# STM32F4DD.net
KiCad netlist of a schematic drawn in Altium Designer
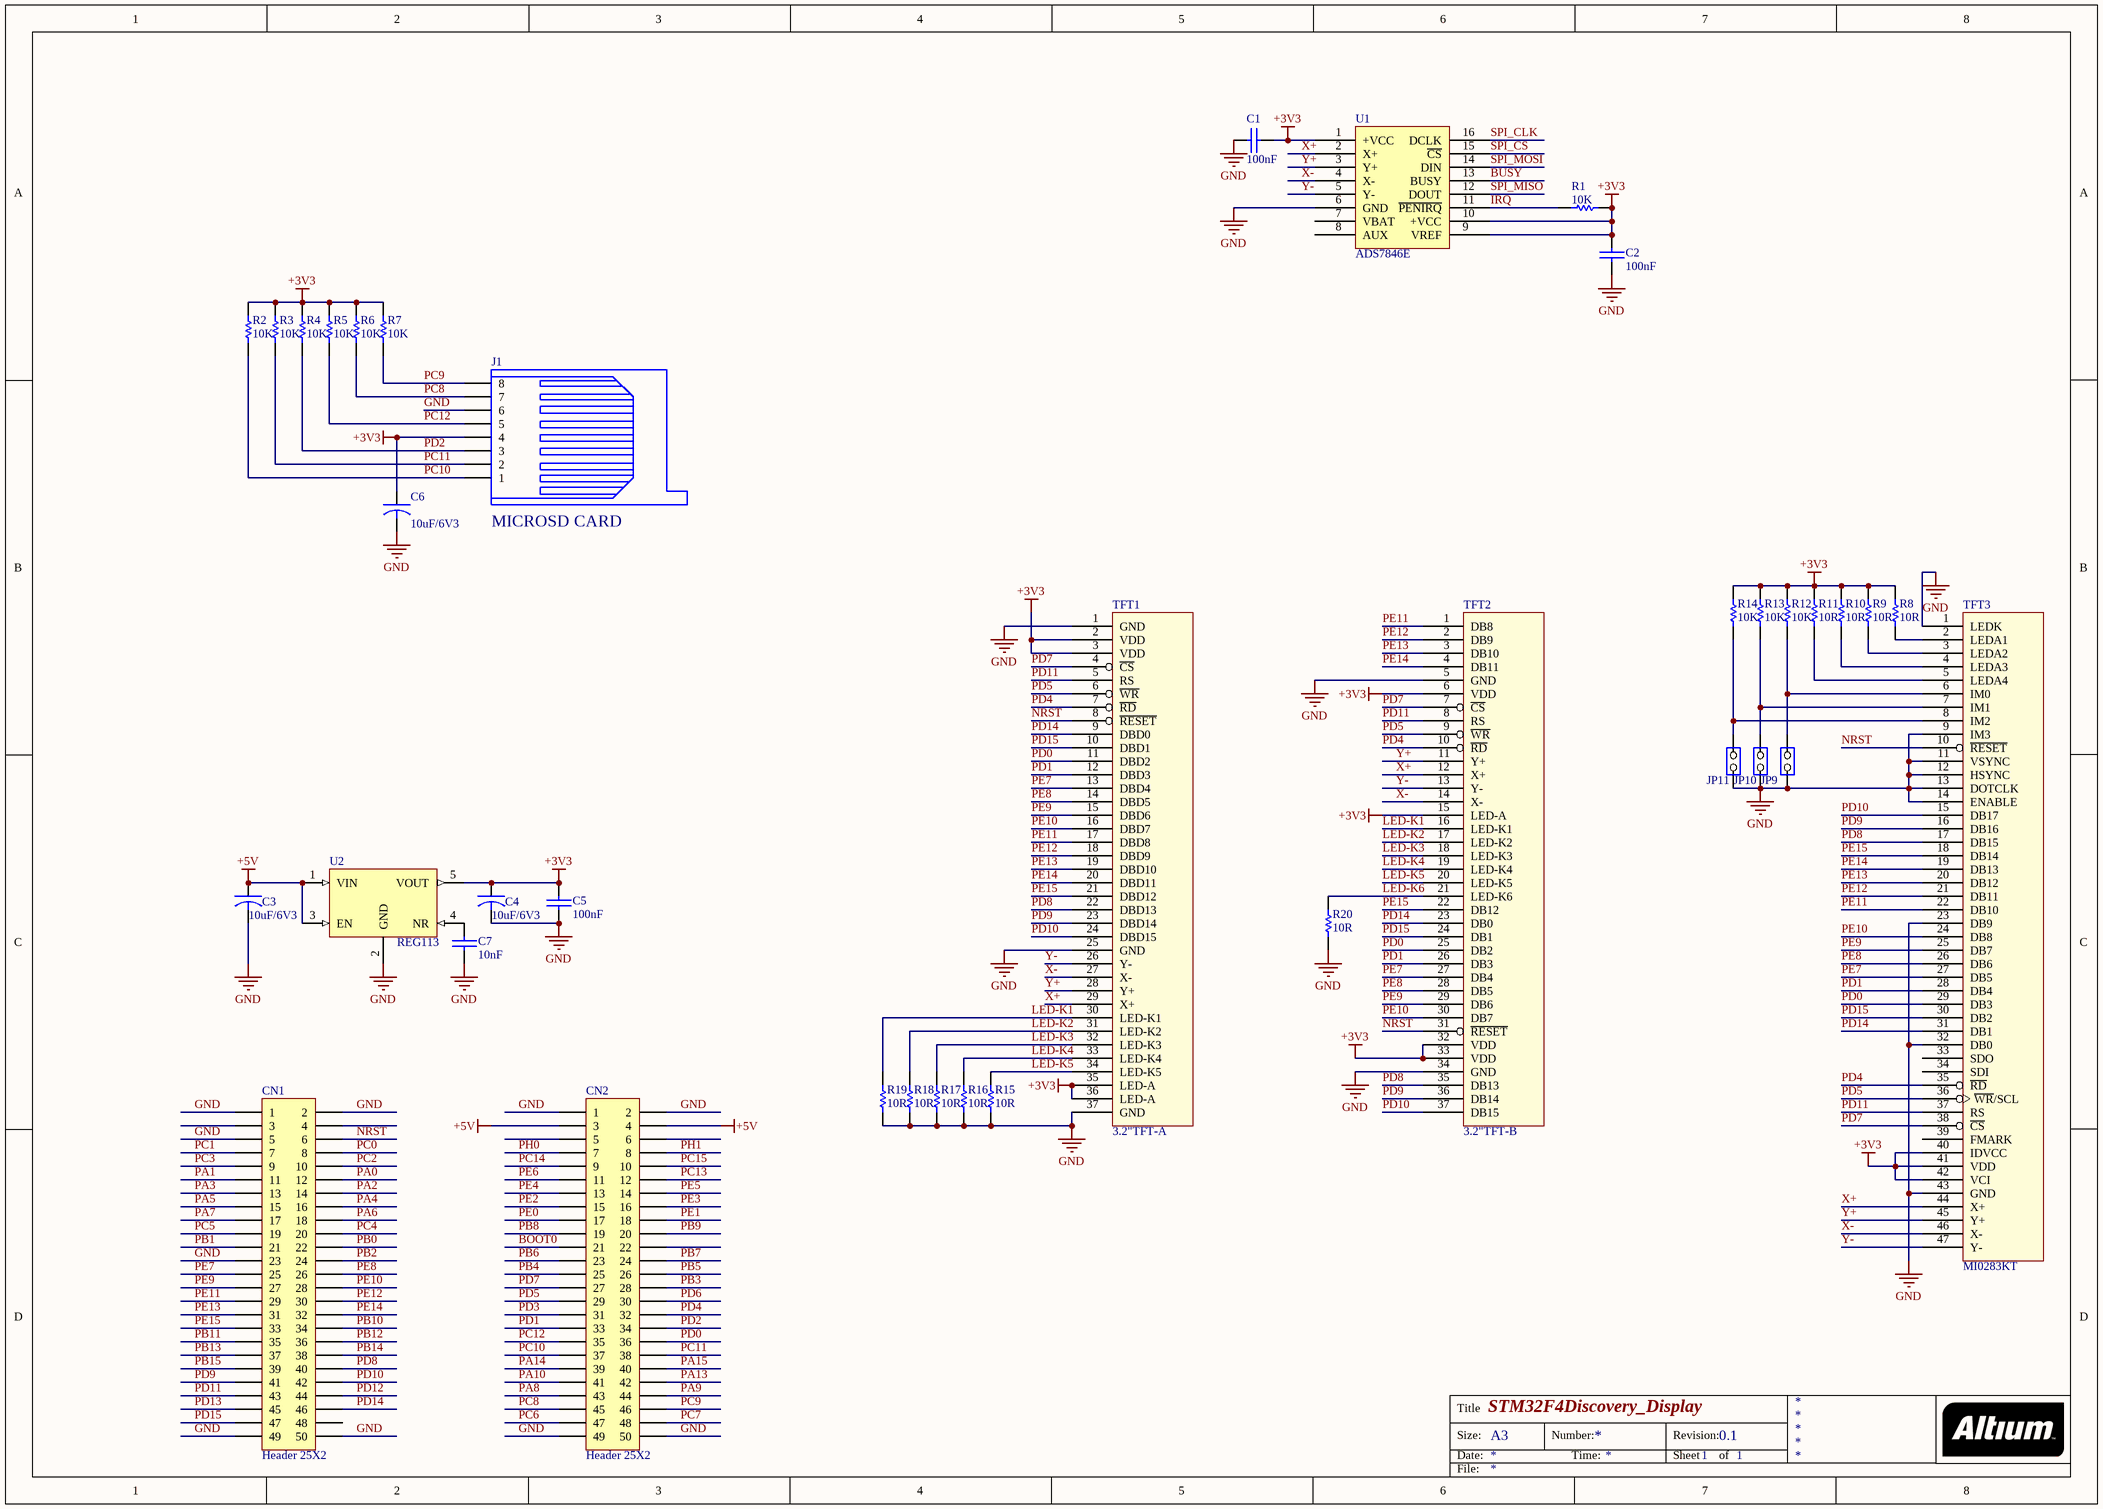
[diagram p0: STM32F4DD.SchDoc]

(export (version "E")
  (design (tool "Eeschema 10.0.6"))
  (components
    (comp (ref "C1")
      (value "100nF")
      (footprint "CAPC1608N")
      (description "Capacitor")
      (libsource (lib "*") (part "CAP"))
    )
    (comp (ref "C2")
      (value "100nF")
      (footprint "CAPC1608N")
      (description "Capacitor")
      (libsource (lib "*") (part "CAP"))
    )
    (comp (ref "C3")
      (value "10uF/6V3")
      (footprint "TC3528-1411")
      (description "Capacitor")
      (fields (field (name "MANUFACTURER") "VISHAY SPRAGUE"))
      (libsource (lib "DAU_Addition") (part "CAPACITOR"))
    )
    (comp (ref "C4")
      (value "10uF/6V3")
      (footprint "TC3528-1411")
      (description "Capacitor")
      (fields (field (name "MANUFACTURER") "VISHAY SPRAGUE"))
      (libsource (lib "DAU_Addition") (part "CAPACITOR"))
    )
    (comp (ref "C5")
      (value "100nF")
      (footprint "CAPC1608N")
      (description "Capacitor")
      (libsource (lib "*") (part "CAP"))
    )
    (comp (ref "C6")
      (value "10uF/6V3")
      (footprint "TC3528-1411")
      (description "Capacitor")
      (fields (field (name "MANUFACTURER") "VISHAY SPRAGUE"))
      (libsource (lib "DAU_Addition") (part "CAPACITOR"))
    )
    (comp (ref "C7")
      (value "10nF")
      (footprint "CAPC1608N")
      (description "Capacitor 10nF")
      (libsource (lib "*") (part "CAP"))
    )
    (comp (ref "CN1")
      (value "Header 25X2")
      (footprint "HDR2X25-TH-SMD")
      (description "Header, 25-Pin, Dual row")
      (fields (field (name "PUBLISHER") "Altium Limited"))
      (libsource (lib "Miscellaneous Connectors") (part "Header 25X2"))
    )
    (comp (ref "CN2")
      (value "Header 25X2")
      (footprint "HDR2X25-TH-SMD")
      (description "Header, 25-Pin, Dual row")
      (fields (field (name "PUBLISHER") "Altium Limited"))
      (libsource (lib "Miscellaneous Connectors") (part "Header 25X2"))
    )
    (comp (ref "J1")
      (value "TFMS08TK-PP")
      (footprint "MEM2060")
      (description "MICRO SD CARD CONNECTOR, PUSH/PUSH TYPE")
      (libsource (lib "*") (part "SMS016AFA5E"))
    )
    (comp (ref "JP9")
      (value "~")
      (footprint "Solder Jumper - NO")
      (description "BOARD-BOARD CONNECTOR HEADER, 2WAY, 1ROW")
      (fields (field (name "MANUFACTURER") "GCT"))
      (libsource (lib "*") (part "JP2"))
    )
    (comp (ref "JP10")
      (value "~")
      (footprint "Solder Jumper - NO")
      (description "BOARD-BOARD CONNECTOR HEADER, 2WAY, 1ROW")
      (fields (field (name "MANUFACTURER") "GCT"))
      (libsource (lib "*") (part "JP2"))
    )
    (comp (ref "JP11")
      (value "~")
      (footprint "Solder Jumper - NO")
      (description "BOARD-BOARD CONNECTOR HEADER, 2WAY, 1ROW")
      (fields (field (name "MANUFACTURER") "GCT"))
      (libsource (lib "*") (part "JP2"))
    )
    (comp (ref "R1")
      (value "10K")
      (footprint "RESC1608N")
      (description "Resistor")
      (fields (field (name "PUBLISHER") "Altium Limited"))
      (libsource (lib "Miscellaneous Devices") (part "Res1"))
    )
    (comp (ref "R2")
      (value "10K")
      (footprint "RESC1608N")
      (description "Resistor")
      (fields (field (name "PUBLISHER") "Altium Limited"))
      (libsource (lib "Miscellaneous Devices") (part "Res1"))
    )
    (comp (ref "R3")
      (value "10K")
      (footprint "RESC1608N")
      (description "Resistor")
      (fields (field (name "PUBLISHER") "Altium Limited"))
      (libsource (lib "Miscellaneous Devices") (part "Res1"))
    )
    (comp (ref "R4")
      (value "10K")
      (footprint "RESC1608N")
      (description "Resistor")
      (fields (field (name "PUBLISHER") "Altium Limited"))
      (libsource (lib "Miscellaneous Devices") (part "Res1"))
    )
    (comp (ref "R5")
      (value "10K")
      (footprint "RESC1608N")
      (description "Resistor")
      (fields (field (name "PUBLISHER") "Altium Limited"))
      (libsource (lib "Miscellaneous Devices") (part "Res1"))
    )
    (comp (ref "R6")
      (value "10K")
      (footprint "RESC1608N")
      (description "Resistor")
      (fields (field (name "PUBLISHER") "Altium Limited"))
      (libsource (lib "Miscellaneous Devices") (part "Res1"))
    )
    (comp (ref "R7")
      (value "10K")
      (footprint "RESC1608N")
      (description "Resistor")
      (fields (field (name "PUBLISHER") "Altium Limited"))
      (libsource (lib "Miscellaneous Devices") (part "Res1"))
    )
    (comp (ref "R8")
      (value "10R")
      (footprint "RESC1608N")
      (description "Resistor")
      (fields (field (name "PUBLISHER") "Altium Limited"))
      (libsource (lib "Miscellaneous Devices") (part "Res1"))
    )
    (comp (ref "R9")
      (value "10R")
      (footprint "RESC1608N")
      (description "Resistor")
      (fields (field (name "PUBLISHER") "Altium Limited"))
      (libsource (lib "Miscellaneous Devices") (part "Res1"))
    )
    (comp (ref "R10")
      (value "10R")
      (footprint "RESC1608N")
      (description "Resistor")
      (fields (field (name "PUBLISHER") "Altium Limited"))
      (libsource (lib "Miscellaneous Devices") (part "Res1"))
    )
    (comp (ref "R11")
      (value "10R")
      (footprint "RESC1608N")
      (description "Resistor")
      (fields (field (name "PUBLISHER") "Altium Limited"))
      (libsource (lib "Miscellaneous Devices") (part "Res1"))
    )
    (comp (ref "R12")
      (value "10K")
      (footprint "RESC1608N")
      (description "Resistor")
      (fields (field (name "PUBLISHER") "Altium Limited"))
      (libsource (lib "Miscellaneous Devices") (part "Res1"))
    )
    (comp (ref "R13")
      (value "10K")
      (footprint "RESC1608N")
      (description "Resistor")
      (fields (field (name "PUBLISHER") "Altium Limited"))
      (libsource (lib "Miscellaneous Devices") (part "Res1"))
    )
    (comp (ref "R14")
      (value "10K")
      (footprint "RESC1608N")
      (description "Resistor")
      (fields (field (name "PUBLISHER") "Altium Limited"))
      (libsource (lib "Miscellaneous Devices") (part "Res1"))
    )
    (comp (ref "R15")
      (value "10R")
      (footprint "RESC1608N")
      (description "Resistor")
      (fields (field (name "PUBLISHER") "Altium Limited"))
      (libsource (lib "Miscellaneous Devices") (part "Res1"))
    )
    (comp (ref "R16")
      (value "10R")
      (footprint "RESC1608N")
      (description "Resistor")
      (fields (field (name "PUBLISHER") "Altium Limited"))
      (libsource (lib "Miscellaneous Devices") (part "Res1"))
    )
    (comp (ref "R17")
      (value "10R")
      (footprint "RESC1608N")
      (description "Resistor")
      (fields (field (name "PUBLISHER") "Altium Limited"))
      (libsource (lib "Miscellaneous Devices") (part "Res1"))
    )
    (comp (ref "R18")
      (value "10R")
      (footprint "RESC1608N")
      (description "Resistor")
      (fields (field (name "PUBLISHER") "Altium Limited"))
      (libsource (lib "Miscellaneous Devices") (part "Res1"))
    )
    (comp (ref "R19")
      (value "10R")
      (footprint "RESC1608N")
      (description "Resistor")
      (fields (field (name "PUBLISHER") "Altium Limited"))
      (libsource (lib "Miscellaneous Devices") (part "Res1"))
    )
    (comp (ref "R20")
      (value "10R")
      (footprint "RESC1608N")
      (description "Resistor")
      (fields (field (name "PUBLISHER") "Altium Limited"))
      (libsource (lib "Miscellaneous Devices") (part "Res1"))
    )
    (comp (ref "TFT1")
      (value "3.2\"TFT-A")
      (footprint "LCD-KWH032Q01-F03")
      (libsource (lib "STM32F4DiscoveryDisplay") (part "3.2{dblquote}TFT-A"))
    )
    (comp (ref "TFT2")
      (value "3.2\"TFT-B")
      (footprint "LCD-KWH032GM02-F05")
      (libsource (lib "STM32F4DiscoveryDisplay") (part "3.2{dblquote}TFT-B"))
    )
    (comp (ref "TFT3")
      (value "MI0283KT")
      (footprint "MI0283KT")
      (description "TFT-G240320UTSW-92W-TP-E")
      (libsource (lib "STM32F4DiscoveryDisplay") (part "MI0283KT"))
    )
    (comp (ref "U1")
      (value "ADS7846E")
      (footprint "SSOP16")
      (description "TOUCH SCREEN CONTROLLER 2.2V TO 5.25V OPERATION")
      (libsource (lib "STM32F4DiscoveryDisplay") (part "ADS7846E"))
    )
    (comp (ref "U2")
      (value "REG113")
      (footprint "SOT95P280X145-5N")
      (description "DMOS  400mA Low-Dropout Regulator")
      (libsource (lib "STM32F4DiscoveryDisplay") (part "REG113"))
    )
  )
  (nets
    (net (code "1") (name "+3V3") (class "Default")
      (node (ref "C1") (pin "2") (pinfunction "2_2") (pintype "passive"))
      (node (ref "C2") (pin "1") (pinfunction "1_1") (pintype "passive"))
      (node (ref "C4") (pin "1") (pinfunction "1_1") (pintype "passive"))
      (node (ref "C5") (pin "2") (pinfunction "2_2") (pintype "passive"))
      (node (ref "C6") (pin "1") (pinfunction "1_1") (pintype "passive"))
      (node (ref "J1") (pin "4") (pinfunction "4_4") (pintype "passive"))
      (node (ref "R1") (pin "2") (pinfunction "2_2") (pintype "passive"))
      (node (ref "R10") (pin "1") (pinfunction "1_1") (pintype "passive"))
      (node (ref "R11") (pin "1") (pinfunction "1_1") (pintype "passive"))
      (node (ref "R12") (pin "2") (pinfunction "2_2") (pintype "passive"))
      (node (ref "R13") (pin "2") (pinfunction "2_2") (pintype "passive"))
      (node (ref "R14") (pin "2") (pinfunction "2_2") (pintype "passive"))
      (node (ref "R2") (pin "2") (pinfunction "2_2") (pintype "passive"))
      (node (ref "R3") (pin "2") (pinfunction "2_2") (pintype "passive"))
      (node (ref "R4") (pin "2") (pinfunction "2_2") (pintype "passive"))
      (node (ref "R5") (pin "2") (pinfunction "2_2") (pintype "passive"))
      (node (ref "R6") (pin "2") (pinfunction "2_2") (pintype "passive"))
      (node (ref "R7") (pin "2") (pinfunction "2_2") (pintype "passive"))
      (node (ref "R8") (pin "1") (pinfunction "1_1") (pintype "passive"))
      (node (ref "R9") (pin "1") (pinfunction "1_1") (pintype "passive"))
      (node (ref "TFT1") (pin "2") (pinfunction "VDD_2") (pintype "passive"))
      (node (ref "TFT1") (pin "3") (pinfunction "VDD_3") (pintype "passive"))
      (node (ref "TFT1") (pin "35") (pinfunction "LED-A_35") (pintype "passive"))
      (node (ref "TFT1") (pin "36") (pinfunction "LED-A_36") (pintype "passive"))
      (node (ref "TFT2") (pin "15") (pinfunction "LED-A_15") (pintype "passive"))
      (node (ref "TFT2") (pin "32") (pinfunction "VDD_32") (pintype "passive"))
      (node (ref "TFT2") (pin "33") (pinfunction "VDD_33") (pintype "passive"))
      (node (ref "TFT2") (pin "6") (pinfunction "VDD_6") (pintype "passive"))
      (node (ref "TFT3") (pin "40") (pinfunction "IDVCC_40") (pintype "passive"))
      (node (ref "TFT3") (pin "41") (pinfunction "VDD_41") (pintype "passive"))
      (node (ref "TFT3") (pin "42") (pinfunction "VCI_42") (pintype "passive"))
      (node (ref "U1") (pin "1") (pinfunction "+VCC_1") (pintype "passive"))
      (node (ref "U1") (pin "10") (pinfunction "+VCC_10") (pintype "passive"))
      (node (ref "U1") (pin "9") (pinfunction "VREF_9") (pintype "passive"))
      (node (ref "U2") (pin "5") (pinfunction "VOUT_5") (pintype "output"))
    )
    (net (code "2") (name "+5V") (class "Default")
      (node (ref "C3") (pin "1") (pinfunction "1_1") (pintype "passive"))
      (node (ref "CN2") (pin "3") (pinfunction "3_3") (pintype "passive"))
      (node (ref "CN2") (pin "4") (pinfunction "4_4") (pintype "passive"))
      (node (ref "U2") (pin "1") (pinfunction "VIN_1") (pintype "input"))
      (node (ref "U2") (pin "3") (pinfunction "EN_3") (pintype "input"))
    )
    (net (code "3") (name "/BOOT0") (class "Default")
      (node (ref "CN2") (pin "21") (pinfunction "21_21") (pintype "passive"))
    )
    (net (code "4") (name "/BUSY") (class "Default")
      (node (ref "U1") (pin "13") (pinfunction "BUSY_13") (pintype "passive"))
    )
    (net (code "5") (name "/IRQ") (class "Default")
      (node (ref "R1") (pin "1") (pinfunction "1_1") (pintype "passive"))
      (node (ref "U1") (pin "11") (pinfunction "~{PENIRQ}_11") (pintype "passive"))
    )
    (net (code "6") (name "/LED-K1") (class "Default")
      (node (ref "R19") (pin "2") (pinfunction "2_2") (pintype "passive"))
      (node (ref "TFT1") (pin "30") (pinfunction "LED-K1_30") (pintype "passive"))
      (node (ref "TFT2") (pin "16") (pinfunction "LED-K1_16") (pintype "passive"))
    )
    (net (code "7") (name "/LED-K2") (class "Default")
      (node (ref "R18") (pin "2") (pinfunction "2_2") (pintype "passive"))
      (node (ref "TFT1") (pin "31") (pinfunction "LED-K2_31") (pintype "passive"))
      (node (ref "TFT2") (pin "17") (pinfunction "LED-K2_17") (pintype "passive"))
    )
    (net (code "8") (name "/LED-K3") (class "Default")
      (node (ref "R17") (pin "2") (pinfunction "2_2") (pintype "passive"))
      (node (ref "TFT1") (pin "32") (pinfunction "LED-K3_32") (pintype "passive"))
      (node (ref "TFT2") (pin "18") (pinfunction "LED-K3_18") (pintype "passive"))
    )
    (net (code "9") (name "/LED-K4") (class "Default")
      (node (ref "R16") (pin "2") (pinfunction "2_2") (pintype "passive"))
      (node (ref "TFT1") (pin "33") (pinfunction "LED-K4_33") (pintype "passive"))
      (node (ref "TFT2") (pin "19") (pinfunction "LED-K4_19") (pintype "passive"))
    )
    (net (code "10") (name "/LED-K5") (class "Default")
      (node (ref "R15") (pin "2") (pinfunction "2_2") (pintype "passive"))
      (node (ref "TFT1") (pin "34") (pinfunction "LED-K5_34") (pintype "passive"))
      (node (ref "TFT2") (pin "20") (pinfunction "LED-K5_20") (pintype "passive"))
    )
    (net (code "11") (name "/LED-K6") (class "Default")
      (node (ref "R20") (pin "2") (pinfunction "2_2") (pintype "passive"))
      (node (ref "TFT2") (pin "21") (pinfunction "LED-K6_21") (pintype "passive"))
    )
    (net (code "12") (name "/NRST") (class "Default")
      (node (ref "CN1") (pin "6") (pinfunction "6_6") (pintype "passive"))
      (node (ref "TFT1") (pin "8") (pinfunction "~{RESET}_8") (pintype "passive"))
      (node (ref "TFT2") (pin "31") (pinfunction "~{RESET}_31") (pintype "passive"))
      (node (ref "TFT3") (pin "10") (pinfunction "~{RESET}_10") (pintype "passive"))
    )
    (net (code "13") (name "/PA0") (class "Default")
      (node (ref "CN1") (pin "12") (pinfunction "12_12") (pintype "passive"))
    )
    (net (code "14") (name "/PA1") (class "Default")
      (node (ref "CN1") (pin "11") (pinfunction "11_11") (pintype "passive"))
    )
    (net (code "15") (name "/PA2") (class "Default")
      (node (ref "CN1") (pin "14") (pinfunction "14_14") (pintype "passive"))
    )
    (net (code "16") (name "/PA3") (class "Default")
      (node (ref "CN1") (pin "13") (pinfunction "13_13") (pintype "passive"))
    )
    (net (code "17") (name "/PA4") (class "Default")
      (node (ref "CN1") (pin "16") (pinfunction "16_16") (pintype "passive"))
    )
    (net (code "18") (name "/PA5") (class "Default")
      (node (ref "CN1") (pin "15") (pinfunction "15_15") (pintype "passive"))
    )
    (net (code "19") (name "/PA6") (class "Default")
      (node (ref "CN1") (pin "18") (pinfunction "18_18") (pintype "passive"))
    )
    (net (code "20") (name "/PA7") (class "Default")
      (node (ref "CN1") (pin "17") (pinfunction "17_17") (pintype "passive"))
    )
    (net (code "21") (name "/PA8") (class "Default")
      (node (ref "CN2") (pin "43") (pinfunction "43_43") (pintype "passive"))
    )
    (net (code "22") (name "/PA9") (class "Default")
      (node (ref "CN2") (pin "44") (pinfunction "44_44") (pintype "passive"))
    )
    (net (code "23") (name "/PA10") (class "Default")
      (node (ref "CN2") (pin "41") (pinfunction "41_41") (pintype "passive"))
    )
    (net (code "24") (name "/PA13") (class "Default")
      (node (ref "CN2") (pin "42") (pinfunction "42_42") (pintype "passive"))
    )
    (net (code "25") (name "/PA14") (class "Default")
      (node (ref "CN2") (pin "39") (pinfunction "39_39") (pintype "passive"))
    )
    (net (code "26") (name "/PA15") (class "Default")
      (node (ref "CN2") (pin "40") (pinfunction "40_40") (pintype "passive"))
    )
    (net (code "27") (name "/PB0") (class "Default")
      (node (ref "CN1") (pin "22") (pinfunction "22_22") (pintype "passive"))
    )
    (net (code "28") (name "/PB1") (class "Default")
      (node (ref "CN1") (pin "21") (pinfunction "21_21") (pintype "passive"))
    )
    (net (code "29") (name "/PB2") (class "Default")
      (node (ref "CN1") (pin "24") (pinfunction "24_24") (pintype "passive"))
    )
    (net (code "30") (name "/PB3") (class "Default")
      (node (ref "CN2") (pin "28") (pinfunction "28_28") (pintype "passive"))
    )
    (net (code "31") (name "/PB4") (class "Default")
      (node (ref "CN2") (pin "25") (pinfunction "25_25") (pintype "passive"))
    )
    (net (code "32") (name "/PB5") (class "Default")
      (node (ref "CN2") (pin "26") (pinfunction "26_26") (pintype "passive"))
    )
    (net (code "33") (name "/PB6") (class "Default")
      (node (ref "CN2") (pin "23") (pinfunction "23_23") (pintype "passive"))
    )
    (net (code "34") (name "/PB7") (class "Default")
      (node (ref "CN2") (pin "24") (pinfunction "24_24") (pintype "passive"))
    )
    (net (code "35") (name "/PB8") (class "Default")
      (node (ref "CN2") (pin "19") (pinfunction "19_19") (pintype "passive"))
    )
    (net (code "36") (name "/PB9") (class "Default")
      (node (ref "CN2") (pin "20") (pinfunction "20_20") (pintype "passive"))
    )
    (net (code "37") (name "/PB10") (class "Default")
      (node (ref "CN1") (pin "34") (pinfunction "34_34") (pintype "passive"))
    )
    (net (code "38") (name "/PB11") (class "Default")
      (node (ref "CN1") (pin "35") (pinfunction "35_35") (pintype "passive"))
    )
    (net (code "39") (name "/PB12") (class "Default")
      (node (ref "CN1") (pin "36") (pinfunction "36_36") (pintype "passive"))
    )
    (net (code "40") (name "/PB13") (class "Default")
      (node (ref "CN1") (pin "37") (pinfunction "37_37") (pintype "passive"))
    )
    (net (code "41") (name "/PB14") (class "Default")
      (node (ref "CN1") (pin "38") (pinfunction "38_38") (pintype "passive"))
    )
    (net (code "42") (name "/PB15") (class "Default")
      (node (ref "CN1") (pin "39") (pinfunction "39_39") (pintype "passive"))
    )
    (net (code "43") (name "/PC0") (class "Default")
      (node (ref "CN1") (pin "8") (pinfunction "8_8") (pintype "passive"))
    )
    (net (code "44") (name "/PC1") (class "Default")
      (node (ref "CN1") (pin "7") (pinfunction "7_7") (pintype "passive"))
    )
    (net (code "45") (name "/PC2") (class "Default")
      (node (ref "CN1") (pin "10") (pinfunction "10_10") (pintype "passive"))
    )
    (net (code "46") (name "/PC3") (class "Default")
      (node (ref "CN1") (pin "9") (pinfunction "9_9") (pintype "passive"))
    )
    (net (code "47") (name "/PC4") (class "Default")
      (node (ref "CN1") (pin "20") (pinfunction "20_20") (pintype "passive"))
    )
    (net (code "48") (name "/PC5") (class "Default")
      (node (ref "CN1") (pin "19") (pinfunction "19_19") (pintype "passive"))
    )
    (net (code "49") (name "/PC6") (class "Default")
      (node (ref "CN2") (pin "47") (pinfunction "47_47") (pintype "passive"))
    )
    (net (code "50") (name "/PC7") (class "Default")
      (node (ref "CN2") (pin "48") (pinfunction "48_48") (pintype "passive"))
    )
    (net (code "51") (name "/PC8") (class "Default")
      (node (ref "CN2") (pin "45") (pinfunction "45_45") (pintype "passive"))
      (node (ref "J1") (pin "7") (pinfunction "7_7") (pintype "passive"))
      (node (ref "R6") (pin "1") (pinfunction "1_1") (pintype "passive"))
    )
    (net (code "52") (name "/PC9") (class "Default")
      (node (ref "CN2") (pin "46") (pinfunction "46_46") (pintype "passive"))
      (node (ref "J1") (pin "8") (pinfunction "8_8") (pintype "passive"))
      (node (ref "R7") (pin "1") (pinfunction "1_1") (pintype "passive"))
    )
    (net (code "53") (name "/PC10") (class "Default")
      (node (ref "CN2") (pin "37") (pinfunction "37_37") (pintype "passive"))
      (node (ref "J1") (pin "1") (pinfunction "1_1") (pintype "passive"))
      (node (ref "R2") (pin "1") (pinfunction "1_1") (pintype "passive"))
    )
    (net (code "54") (name "/PC11") (class "Default")
      (node (ref "CN2") (pin "38") (pinfunction "38_38") (pintype "passive"))
      (node (ref "J1") (pin "2") (pinfunction "2_2") (pintype "passive"))
      (node (ref "R3") (pin "1") (pinfunction "1_1") (pintype "passive"))
    )
    (net (code "55") (name "/PC12") (class "Default")
      (node (ref "CN2") (pin "35") (pinfunction "35_35") (pintype "passive"))
      (node (ref "J1") (pin "5") (pinfunction "5_5") (pintype "passive"))
      (node (ref "R5") (pin "1") (pinfunction "1_1") (pintype "passive"))
    )
    (net (code "56") (name "/PC13") (class "Default")
      (node (ref "CN2") (pin "12") (pinfunction "12_12") (pintype "passive"))
    )
    (net (code "57") (name "/PC14") (class "Default")
      (node (ref "CN2") (pin "9") (pinfunction "9_9") (pintype "passive"))
    )
    (net (code "58") (name "/PC15") (class "Default")
      (node (ref "CN2") (pin "10") (pinfunction "10_10") (pintype "passive"))
    )
    (net (code "59") (name "/PD0") (class "Default")
      (node (ref "CN2") (pin "36") (pinfunction "36_36") (pintype "passive"))
      (node (ref "TFT1") (pin "11") (pinfunction "DBD2_11") (pintype "passive"))
      (node (ref "TFT2") (pin "25") (pinfunction "DB2_25") (pintype "passive"))
      (node (ref "TFT3") (pin "29") (pinfunction "DB3_29") (pintype "passive"))
    )
    (net (code "60") (name "/PD1") (class "Default")
      (node (ref "CN2") (pin "33") (pinfunction "33_33") (pintype "passive"))
      (node (ref "TFT1") (pin "12") (pinfunction "DBD3_12") (pintype "passive"))
      (node (ref "TFT2") (pin "26") (pinfunction "DB3_26") (pintype "passive"))
      (node (ref "TFT3") (pin "28") (pinfunction "DB4_28") (pintype "passive"))
    )
    (net (code "61") (name "/PD2") (class "Default")
      (node (ref "CN2") (pin "34") (pinfunction "34_34") (pintype "passive"))
      (node (ref "J1") (pin "3") (pinfunction "3_3") (pintype "passive"))
      (node (ref "R4") (pin "1") (pinfunction "1_1") (pintype "passive"))
    )
    (net (code "62") (name "/PD3") (class "Default")
      (node (ref "CN2") (pin "31") (pinfunction "31_31") (pintype "passive"))
    )
    (net (code "63") (name "/PD4") (class "Default")
      (node (ref "CN2") (pin "32") (pinfunction "32_32") (pintype "passive"))
      (node (ref "TFT1") (pin "7") (pinfunction "~{RD}_7") (pintype "passive"))
      (node (ref "TFT2") (pin "10") (pinfunction "~{RD}_10") (pintype "passive"))
      (node (ref "TFT3") (pin "35") (pinfunction "~{RD}_35") (pintype "passive"))
    )
    (net (code "64") (name "/PD5") (class "Default")
      (node (ref "CN2") (pin "29") (pinfunction "29_29") (pintype "passive"))
      (node (ref "TFT1") (pin "6") (pinfunction "~{WR}_6") (pintype "passive"))
      (node (ref "TFT2") (pin "9") (pinfunction "~{WR}_9") (pintype "passive"))
      (node (ref "TFT3") (pin "36") (pinfunction "~{WR}/SCL_36") (pintype "passive"))
    )
    (net (code "65") (name "/PD6") (class "Default")
      (node (ref "CN2") (pin "30") (pinfunction "30_30") (pintype "passive"))
    )
    (net (code "66") (name "/PD7") (class "Default")
      (node (ref "CN2") (pin "27") (pinfunction "27_27") (pintype "passive"))
      (node (ref "TFT1") (pin "4") (pinfunction "~{CS}_4") (pintype "passive"))
      (node (ref "TFT2") (pin "7") (pinfunction "~{CS}_7") (pintype "passive"))
      (node (ref "TFT3") (pin "38") (pinfunction "~{CS}_38") (pintype "passive"))
    )
    (net (code "67") (name "/PD8") (class "Default")
      (node (ref "CN1") (pin "40") (pinfunction "40_40") (pintype "passive"))
      (node (ref "TFT1") (pin "22") (pinfunction "DBD13_22") (pintype "passive"))
      (node (ref "TFT2") (pin "35") (pinfunction "DB13_35") (pintype "power_in"))
      (node (ref "TFT3") (pin "17") (pinfunction "DB15_17") (pintype "passive"))
    )
    (net (code "68") (name "/PD9") (class "Default")
      (node (ref "CN1") (pin "41") (pinfunction "41_41") (pintype "passive"))
      (node (ref "TFT1") (pin "23") (pinfunction "DBD14_23") (pintype "passive"))
      (node (ref "TFT2") (pin "36") (pinfunction "DB14_36") (pintype "power_in"))
      (node (ref "TFT3") (pin "16") (pinfunction "DB16_16") (pintype "passive"))
    )
    (net (code "69") (name "/PD10") (class "Default")
      (node (ref "CN1") (pin "42") (pinfunction "42_42") (pintype "passive"))
      (node (ref "TFT1") (pin "24") (pinfunction "DBD15_24") (pintype "passive"))
      (node (ref "TFT2") (pin "37") (pinfunction "DB15_37") (pintype "power_in"))
      (node (ref "TFT3") (pin "15") (pinfunction "DB17_15") (pintype "passive"))
    )
    (net (code "70") (name "/PD11") (class "Default")
      (node (ref "CN1") (pin "43") (pinfunction "43_43") (pintype "passive"))
      (node (ref "TFT1") (pin "5") (pinfunction "RS_5") (pintype "passive"))
      (node (ref "TFT2") (pin "8") (pinfunction "RS_8") (pintype "passive"))
      (node (ref "TFT3") (pin "37") (pinfunction "RS_37") (pintype "passive"))
    )
    (net (code "71") (name "/PD12") (class "Default")
      (node (ref "CN1") (pin "44") (pinfunction "44_44") (pintype "passive"))
    )
    (net (code "72") (name "/PD13") (class "Default")
      (node (ref "CN1") (pin "45") (pinfunction "45_45") (pintype "passive"))
    )
    (net (code "73") (name "/PD14") (class "Default")
      (node (ref "CN1") (pin "46") (pinfunction "46_46") (pintype "passive"))
      (node (ref "TFT1") (pin "9") (pinfunction "DBD0_9") (pintype "passive"))
      (node (ref "TFT2") (pin "23") (pinfunction "DB0_23") (pintype "passive"))
      (node (ref "TFT3") (pin "31") (pinfunction "DB1_31") (pintype "passive"))
    )
    (net (code "74") (name "/PD15") (class "Default")
      (node (ref "CN1") (pin "47") (pinfunction "47_47") (pintype "passive"))
      (node (ref "TFT1") (pin "10") (pinfunction "DBD1_10") (pintype "passive"))
      (node (ref "TFT2") (pin "24") (pinfunction "DB1_24") (pintype "passive"))
      (node (ref "TFT3") (pin "30") (pinfunction "DB2_30") (pintype "passive"))
    )
    (net (code "75") (name "/PE0") (class "Default")
      (node (ref "CN2") (pin "17") (pinfunction "17_17") (pintype "passive"))
    )
    (net (code "76") (name "/PE1") (class "Default")
      (node (ref "CN2") (pin "18") (pinfunction "18_18") (pintype "passive"))
    )
    (net (code "77") (name "/PE2") (class "Default")
      (node (ref "CN2") (pin "15") (pinfunction "15_15") (pintype "passive"))
    )
    (net (code "78") (name "/PE3") (class "Default")
      (node (ref "CN2") (pin "16") (pinfunction "16_16") (pintype "passive"))
    )
    (net (code "79") (name "/PE4") (class "Default")
      (node (ref "CN2") (pin "13") (pinfunction "13_13") (pintype "passive"))
    )
    (net (code "80") (name "/PE5") (class "Default")
      (node (ref "CN2") (pin "14") (pinfunction "14_14") (pintype "passive"))
    )
    (net (code "81") (name "/PE6") (class "Default")
      (node (ref "CN2") (pin "11") (pinfunction "11_11") (pintype "passive"))
    )
    (net (code "82") (name "/PE7") (class "Default")
      (node (ref "CN1") (pin "25") (pinfunction "25_25") (pintype "passive"))
      (node (ref "TFT1") (pin "13") (pinfunction "DBD4_13") (pintype "passive"))
      (node (ref "TFT2") (pin "27") (pinfunction "DB4_27") (pintype "passive"))
      (node (ref "TFT3") (pin "27") (pinfunction "DB5_27") (pintype "passive"))
    )
    (net (code "83") (name "/PE8") (class "Default")
      (node (ref "CN1") (pin "26") (pinfunction "26_26") (pintype "passive"))
      (node (ref "TFT1") (pin "14") (pinfunction "DBD5_14") (pintype "passive"))
      (node (ref "TFT2") (pin "28") (pinfunction "DB5_28") (pintype "passive"))
      (node (ref "TFT3") (pin "26") (pinfunction "DB6_26") (pintype "passive"))
    )
    (net (code "84") (name "/PE9") (class "Default")
      (node (ref "CN1") (pin "27") (pinfunction "27_27") (pintype "passive"))
      (node (ref "TFT1") (pin "15") (pinfunction "DBD6_15") (pintype "passive"))
      (node (ref "TFT2") (pin "29") (pinfunction "DB6_29") (pintype "passive"))
      (node (ref "TFT3") (pin "25") (pinfunction "DB7_25") (pintype "passive"))
    )
    (net (code "85") (name "/PE10") (class "Default")
      (node (ref "CN1") (pin "28") (pinfunction "28_28") (pintype "passive"))
      (node (ref "TFT1") (pin "16") (pinfunction "DBD7_16") (pintype "passive"))
      (node (ref "TFT2") (pin "30") (pinfunction "DB7_30") (pintype "passive"))
      (node (ref "TFT3") (pin "24") (pinfunction "DB8_24") (pintype "passive"))
    )
    (net (code "86") (name "/PE11") (class "Default")
      (node (ref "CN1") (pin "29") (pinfunction "29_29") (pintype "passive"))
      (node (ref "TFT1") (pin "17") (pinfunction "DBD8_17") (pintype "passive"))
      (node (ref "TFT2") (pin "1") (pinfunction "DB8_1") (pintype "power_in"))
      (node (ref "TFT3") (pin "22") (pinfunction "DB10_22") (pintype "passive"))
    )
    (net (code "87") (name "/PE12") (class "Default")
      (node (ref "CN1") (pin "30") (pinfunction "30_30") (pintype "passive"))
      (node (ref "TFT1") (pin "18") (pinfunction "DBD9_18") (pintype "passive"))
      (node (ref "TFT2") (pin "2") (pinfunction "DB9_2") (pintype "power_in"))
      (node (ref "TFT3") (pin "21") (pinfunction "DB11_21") (pintype "passive"))
    )
    (net (code "88") (name "/PE13") (class "Default")
      (node (ref "CN1") (pin "31") (pinfunction "31_31") (pintype "passive"))
      (node (ref "TFT1") (pin "19") (pinfunction "DBD10_19") (pintype "passive"))
      (node (ref "TFT2") (pin "3") (pinfunction "DB10_3") (pintype "power_in"))
      (node (ref "TFT3") (pin "20") (pinfunction "DB12_20") (pintype "passive"))
    )
    (net (code "89") (name "/PE14") (class "Default")
      (node (ref "CN1") (pin "32") (pinfunction "32_32") (pintype "passive"))
      (node (ref "TFT1") (pin "20") (pinfunction "DBD11_20") (pintype "passive"))
      (node (ref "TFT2") (pin "4") (pinfunction "DB11_4") (pintype "power_in"))
      (node (ref "TFT3") (pin "19") (pinfunction "DB13_19") (pintype "passive"))
    )
    (net (code "90") (name "/PE15") (class "Default")
      (node (ref "CN1") (pin "33") (pinfunction "33_33") (pintype "passive"))
      (node (ref "TFT1") (pin "21") (pinfunction "DBD12_21") (pintype "passive"))
      (node (ref "TFT2") (pin "22") (pinfunction "DB12_22") (pintype "passive"))
      (node (ref "TFT3") (pin "18") (pinfunction "DB14_18") (pintype "passive"))
    )
    (net (code "91") (name "/PH0") (class "Default")
      (node (ref "CN2") (pin "7") (pinfunction "7_7") (pintype "passive"))
    )
    (net (code "92") (name "/PH1") (class "Default")
      (node (ref "CN2") (pin "8") (pinfunction "8_8") (pintype "passive"))
    )
    (net (code "93") (name "/SPI_CLK") (class "Default")
      (node (ref "U1") (pin "16") (pinfunction "DCLK_16") (pintype "passive"))
    )
    (net (code "94") (name "/SPI_CS") (class "Default")
      (node (ref "U1") (pin "15") (pinfunction "~{CS}_15") (pintype "passive"))
    )
    (net (code "95") (name "/SPI_MISO") (class "Default")
      (node (ref "U1") (pin "12") (pinfunction "DOUT_12") (pintype "passive"))
    )
    (net (code "96") (name "/SPI_MOSI") (class "Default")
      (node (ref "U1") (pin "14") (pinfunction "DIN_14") (pintype "passive"))
    )
    (net (code "97") (name "/X+") (class "Default")
      (node (ref "TFT1") (pin "29") (pinfunction "X+_29") (pintype "passive"))
      (node (ref "TFT2") (pin "12") (pinfunction "X+_12") (pintype "passive"))
      (node (ref "TFT3") (pin "44") (pinfunction "X+_44") (pintype "passive"))
      (node (ref "U1") (pin "2") (pinfunction "X+_2") (pintype "passive"))
    )
    (net (code "98") (name "/X-") (class "Default")
      (node (ref "TFT1") (pin "27") (pinfunction "X-_27") (pintype "passive"))
      (node (ref "TFT2") (pin "14") (pinfunction "X-_14") (pintype "passive"))
      (node (ref "TFT3") (pin "46") (pinfunction "X-_46") (pintype "passive"))
      (node (ref "U1") (pin "4") (pinfunction "X-_4") (pintype "passive"))
    )
    (net (code "99") (name "/Y+") (class "Default")
      (node (ref "TFT1") (pin "28") (pinfunction "Y+_28") (pintype "passive"))
      (node (ref "TFT2") (pin "11") (pinfunction "Y+_11") (pintype "passive"))
      (node (ref "TFT3") (pin "45") (pinfunction "Y+_45") (pintype "passive"))
      (node (ref "U1") (pin "3") (pinfunction "Y+_3") (pintype "passive"))
    )
    (net (code "100") (name "/Y-") (class "Default")
      (node (ref "TFT1") (pin "26") (pinfunction "Y-_26") (pintype "passive"))
      (node (ref "TFT2") (pin "13") (pinfunction "Y-_13") (pintype "passive"))
      (node (ref "TFT3") (pin "47") (pinfunction "Y-_47") (pintype "passive"))
      (node (ref "U1") (pin "5") (pinfunction "Y-_5") (pintype "passive"))
    )
    (net (code "101") (name "GND") (class "Default")
      (node (ref "C1") (pin "1") (pinfunction "1_1") (pintype "passive"))
      (node (ref "C2") (pin "2") (pinfunction "2_2") (pintype "passive"))
      (node (ref "C3") (pin "2") (pinfunction "2_2") (pintype "passive"))
      (node (ref "C4") (pin "2") (pinfunction "2_2") (pintype "passive"))
      (node (ref "C5") (pin "1") (pinfunction "1_1") (pintype "passive"))
      (node (ref "C6") (pin "2") (pinfunction "2_2") (pintype "passive"))
      (node (ref "C7") (pin "2") (pinfunction "2_2") (pintype "passive"))
      (node (ref "CN1") (pin "1") (pinfunction "1_1") (pintype "passive"))
      (node (ref "CN1") (pin "2") (pinfunction "2_2") (pintype "passive"))
      (node (ref "CN1") (pin "23") (pinfunction "23_23") (pintype "passive"))
      (node (ref "CN1") (pin "49") (pinfunction "49_49") (pintype "passive"))
      (node (ref "CN1") (pin "5") (pinfunction "5_5") (pintype "passive"))
      (node (ref "CN1") (pin "50") (pinfunction "50_50") (pintype "passive"))
      (node (ref "CN2") (pin "1") (pinfunction "1_1") (pintype "passive"))
      (node (ref "CN2") (pin "2") (pinfunction "2_2") (pintype "passive"))
      (node (ref "CN2") (pin "49") (pinfunction "49_49") (pintype "passive"))
      (node (ref "CN2") (pin "50") (pinfunction "50_50") (pintype "passive"))
      (node (ref "J1") (pin "6") (pinfunction "6_6") (pintype "passive"))
      (node (ref "JP10") (pin "1") (pinfunction "COMMON_1") (pintype "passive"))
      (node (ref "JP11") (pin "1") (pinfunction "COMMON_1") (pintype "passive"))
      (node (ref "JP9") (pin "1") (pinfunction "COMMON_1") (pintype "passive"))
      (node (ref "R15") (pin "1") (pinfunction "1_1") (pintype "passive"))
      (node (ref "R16") (pin "1") (pinfunction "1_1") (pintype "passive"))
      (node (ref "R17") (pin "1") (pinfunction "1_1") (pintype "passive"))
      (node (ref "R18") (pin "1") (pinfunction "1_1") (pintype "passive"))
      (node (ref "R19") (pin "1") (pinfunction "1_1") (pintype "passive"))
      (node (ref "R20") (pin "1") (pinfunction "1_1") (pintype "passive"))
      (node (ref "TFT1") (pin "1") (pinfunction "GND_1") (pintype "power_in"))
      (node (ref "TFT1") (pin "25") (pinfunction "GND_25") (pintype "power_in"))
      (node (ref "TFT1") (pin "37") (pinfunction "GND_37") (pintype "power_in"))
      (node (ref "TFT2") (pin "34") (pinfunction "GND_34") (pintype "power_in"))
      (node (ref "TFT2") (pin "5") (pinfunction "GND_5") (pintype "power_in"))
      (node (ref "TFT3") (pin "1") (pinfunction "LEDK_1") (pintype "passive"))
      (node (ref "TFT3") (pin "11") (pinfunction "VSYNC_11") (pintype "passive"))
      (node (ref "TFT3") (pin "12") (pinfunction "HSYNC_12") (pintype "passive"))
      (node (ref "TFT3") (pin "13") (pinfunction "DOTCLK_13") (pintype "passive"))
      (node (ref "TFT3") (pin "14") (pinfunction "ENABLE_14") (pintype "passive"))
      (node (ref "TFT3") (pin "23") (pinfunction "DB9_23") (pintype "passive"))
      (node (ref "TFT3") (pin "32") (pinfunction "DB0_32") (pintype "passive"))
      (node (ref "TFT3") (pin "43") (pinfunction "GND_43") (pintype "passive"))
      (node (ref "TFT3") (pin "9") (pinfunction "IM3_9") (pintype "passive"))
      (node (ref "U1") (pin "6") (pinfunction "GND_6") (pintype "passive"))
      (node (ref "U2") (pin "2") (pinfunction "GND_2") (pintype "power_in"))
    )
    (net (code "102") (name "Net-(JP9-NO)") (class "Default")
      (node (ref "JP9") (pin "2") (pinfunction "NO_2") (pintype "passive"))
      (node (ref "R12") (pin "1") (pinfunction "1_1") (pintype "passive"))
      (node (ref "TFT3") (pin "6") (pinfunction "IM0_6") (pintype "passive"))
    )
    (net (code "103") (name "Net-(JP10-NO)") (class "Default")
      (node (ref "JP10") (pin "2") (pinfunction "NO_2") (pintype "passive"))
      (node (ref "R13") (pin "1") (pinfunction "1_1") (pintype "passive"))
      (node (ref "TFT3") (pin "7") (pinfunction "IM1_7") (pintype "passive"))
    )
    (net (code "104") (name "Net-(JP11-NO)") (class "Default")
      (node (ref "JP11") (pin "2") (pinfunction "NO_2") (pintype "passive"))
      (node (ref "R14") (pin "1") (pinfunction "1_1") (pintype "passive"))
      (node (ref "TFT3") (pin "8") (pinfunction "IM2_8") (pintype "passive"))
    )
    (net (code "105") (name "Net-(TFT3-LEDA1)") (class "Default")
      (node (ref "R8") (pin "2") (pinfunction "2_2") (pintype "passive"))
      (node (ref "TFT3") (pin "2") (pinfunction "LEDA1_2") (pintype "passive"))
    )
    (net (code "106") (name "Net-(TFT3-LEDA2)") (class "Default")
      (node (ref "R9") (pin "2") (pinfunction "2_2") (pintype "passive"))
      (node (ref "TFT3") (pin "3") (pinfunction "LEDA2_3") (pintype "passive"))
    )
    (net (code "107") (name "Net-(TFT3-LEDA3)") (class "Default")
      (node (ref "R10") (pin "2") (pinfunction "2_2") (pintype "passive"))
      (node (ref "TFT3") (pin "4") (pinfunction "LEDA3_4") (pintype "passive"))
    )
    (net (code "108") (name "Net-(TFT3-LEDA4)") (class "Default")
      (node (ref "R11") (pin "2") (pinfunction "2_2") (pintype "passive"))
      (node (ref "TFT3") (pin "5") (pinfunction "LEDA4_5") (pintype "passive"))
    )
    (net (code "109") (name "Net-(U2-NR)") (class "Default")
      (node (ref "C7") (pin "1") (pinfunction "1_1") (pintype "passive"))
      (node (ref "U2") (pin "4") (pinfunction "NR_4") (pintype "input"))
    )
    (net (code "110") (name "unconnected-(CN1-Pad3)") (class "Default")
      (node (ref "CN1") (pin "3") (pinfunction "3_3") (pintype "passive"))
    )
    (net (code "111") (name "unconnected-(CN1-Pad4)") (class "Default")
      (node (ref "CN1") (pin "4") (pinfunction "4_4") (pintype "passive"))
    )
    (net (code "112") (name "unconnected-(CN1-Pad48)") (class "Default")
      (node (ref "CN1") (pin "48") (pinfunction "48_48") (pintype "passive"))
    )
    (net (code "113") (name "unconnected-(CN2-Pad5)") (class "Default")
      (node (ref "CN2") (pin "5") (pinfunction "5_5") (pintype "passive"))
    )
    (net (code "114") (name "unconnected-(CN2-Pad6)") (class "Default")
      (node (ref "CN2") (pin "6") (pinfunction "6_6") (pintype "passive"))
    )
    (net (code "115") (name "unconnected-(CN2-Pad22)") (class "Default")
      (node (ref "CN2") (pin "22") (pinfunction "22_22") (pintype "passive"))
    )
    (net (code "116") (name "unconnected-(TFT3-FMARK-Pad39)") (class "Default")
      (node (ref "TFT3") (pin "39") (pinfunction "FMARK_39") (pintype "passive"))
    )
    (net (code "117") (name "unconnected-(TFT3-SDI-Pad34)") (class "Default")
      (node (ref "TFT3") (pin "34") (pinfunction "SDI_34") (pintype "passive"))
    )
    (net (code "118") (name "unconnected-(TFT3-SDO-Pad33)") (class "Default")
      (node (ref "TFT3") (pin "33") (pinfunction "SDO_33") (pintype "passive"))
    )
    (net (code "119") (name "unconnected-(U1-AUX-Pad8)") (class "Default")
      (node (ref "U1") (pin "8") (pinfunction "AUX_8") (pintype "passive"))
    )
    (net (code "120") (name "unconnected-(U1-VBAT-Pad7)") (class "Default")
      (node (ref "U1") (pin "7") (pinfunction "VBAT_7") (pintype "passive"))
    )
  )
)
